# IO_Block.net
KiCad netlist of a schematic drawn in Altium Designer
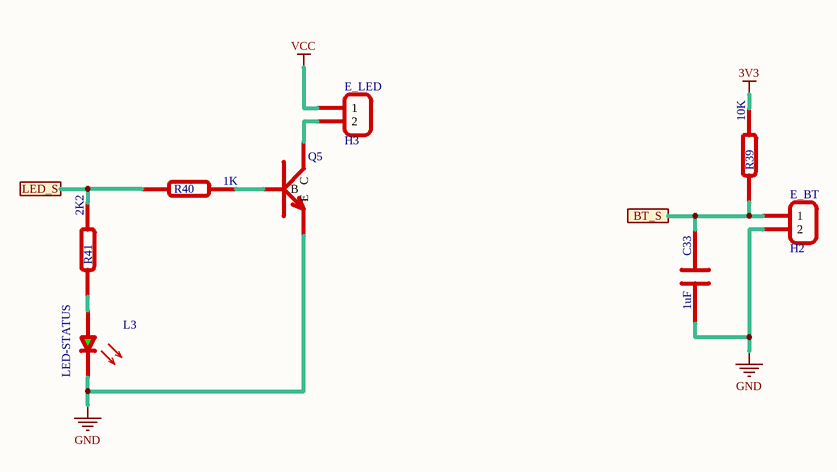
[diagram p0: IO_Block.SchDoc]

(export (version "E")
  (design (tool "Eeschema 10.0.6"))
  (components
    (comp (ref "C33")
      (value "1uF")
      (footprint "C0603")
      (description "Ceramic Capacitor")
      (libsource (lib "CTAI-Library") (part "CAP-CER"))
    )
    (comp (ref "H2")
      (value "E_BT")
      (footprint "XH-2.54-2P")
      (description "Connector 2 Pole")
      (libsource (lib "CTAI-Library") (part "CONN-2P"))
    )
    (comp (ref "H3")
      (value "E_LED")
      (footprint "XH-2.54-2P")
      (description "Connector 2 Pole")
      (libsource (lib "CTAI-Library") (part "CONN-2P"))
    )
    (comp (ref "L3")
      (value "LED-STATUS")
      (footprint "LED-0805-GREEN")
      (description "Green Light Emiter Diode")
      (libsource (lib "CTAI-Library") (part "LED-Green"))
    )
    (comp (ref "Q5")
      (value "S8050")
      (footprint "TO-92A")
      (description "NPN Transistors 0.5A Collector to Emitter 25V")
      (libsource (lib "CTAI-Library") (part "S8050"))
    )
    (comp (ref "R39")
      (value "10K")
      (footprint "R0603")
      (description "Resistor")
      (libsource (lib "CTAI-Library") (part "Resistor"))
    )
    (comp (ref "R40")
      (value "1K")
      (footprint "R0603")
      (description "Resistor")
      (libsource (lib "CTAI-Library") (part "Resistor"))
    )
    (comp (ref "R41")
      (value "2K2")
      (footprint "R0603")
      (description "Resistor")
      (libsource (lib "CTAI-Library") (part "Resistor"))
    )
  )
  (nets
    (net (code "1") (name "/BT_S") (class "Default")
      (node (ref "C33") (pin "2") (pintype "passive"))
      (node (ref "H2") (pin "1") (pinfunction "1_1") (pintype "passive"))
      (node (ref "R39") (pin "1") (pinfunction "1_1") (pintype "passive"))
    )
    (net (code "2") (name "/LED_S") (class "Default")
      (node (ref "R40") (pin "1") (pinfunction "1_1") (pintype "passive"))
      (node (ref "R41") (pin "2") (pinfunction "2_2") (pintype "passive"))
    )
    (net (code "3") (name "3V3") (class "Default")
      (node (ref "R39") (pin "2") (pinfunction "2_2") (pintype "passive"))
    )
    (net (code "4") (name "GND") (class "Default")
      (node (ref "C33") (pin "1") (pintype "passive"))
      (node (ref "H2") (pin "2") (pinfunction "2_2") (pintype "passive"))
      (node (ref "L3") (pin "2") (pinfunction "K_2") (pintype "passive"))
      (node (ref "Q5") (pin "2") (pinfunction "E_2") (pintype "passive"))
    )
    (net (code "5") (name "Net-(L3-A)") (class "Default")
      (node (ref "L3") (pin "1") (pinfunction "A_1") (pintype "passive"))
      (node (ref "R41") (pin "1") (pinfunction "1_1") (pintype "passive"))
    )
    (net (code "6") (name "Net-(Q5-B)") (class "Default")
      (node (ref "Q5") (pin "1") (pinfunction "B_1") (pintype "passive"))
      (node (ref "R40") (pin "2") (pinfunction "2_2") (pintype "passive"))
    )
    (net (code "7") (name "Net-(Q5-C)") (class "Default")
      (node (ref "H3") (pin "2") (pinfunction "2_2") (pintype "passive"))
      (node (ref "Q5") (pin "3") (pinfunction "C_3") (pintype "passive"))
    )
    (net (code "8") (name "VCC") (class "Default")
      (node (ref "H3") (pin "1") (pinfunction "1_1") (pintype "passive"))
    )
  )
)
